# SCH_Genie-V1_2024-08-11.net
KiCad netlist of a schematic drawn in EasyEDA
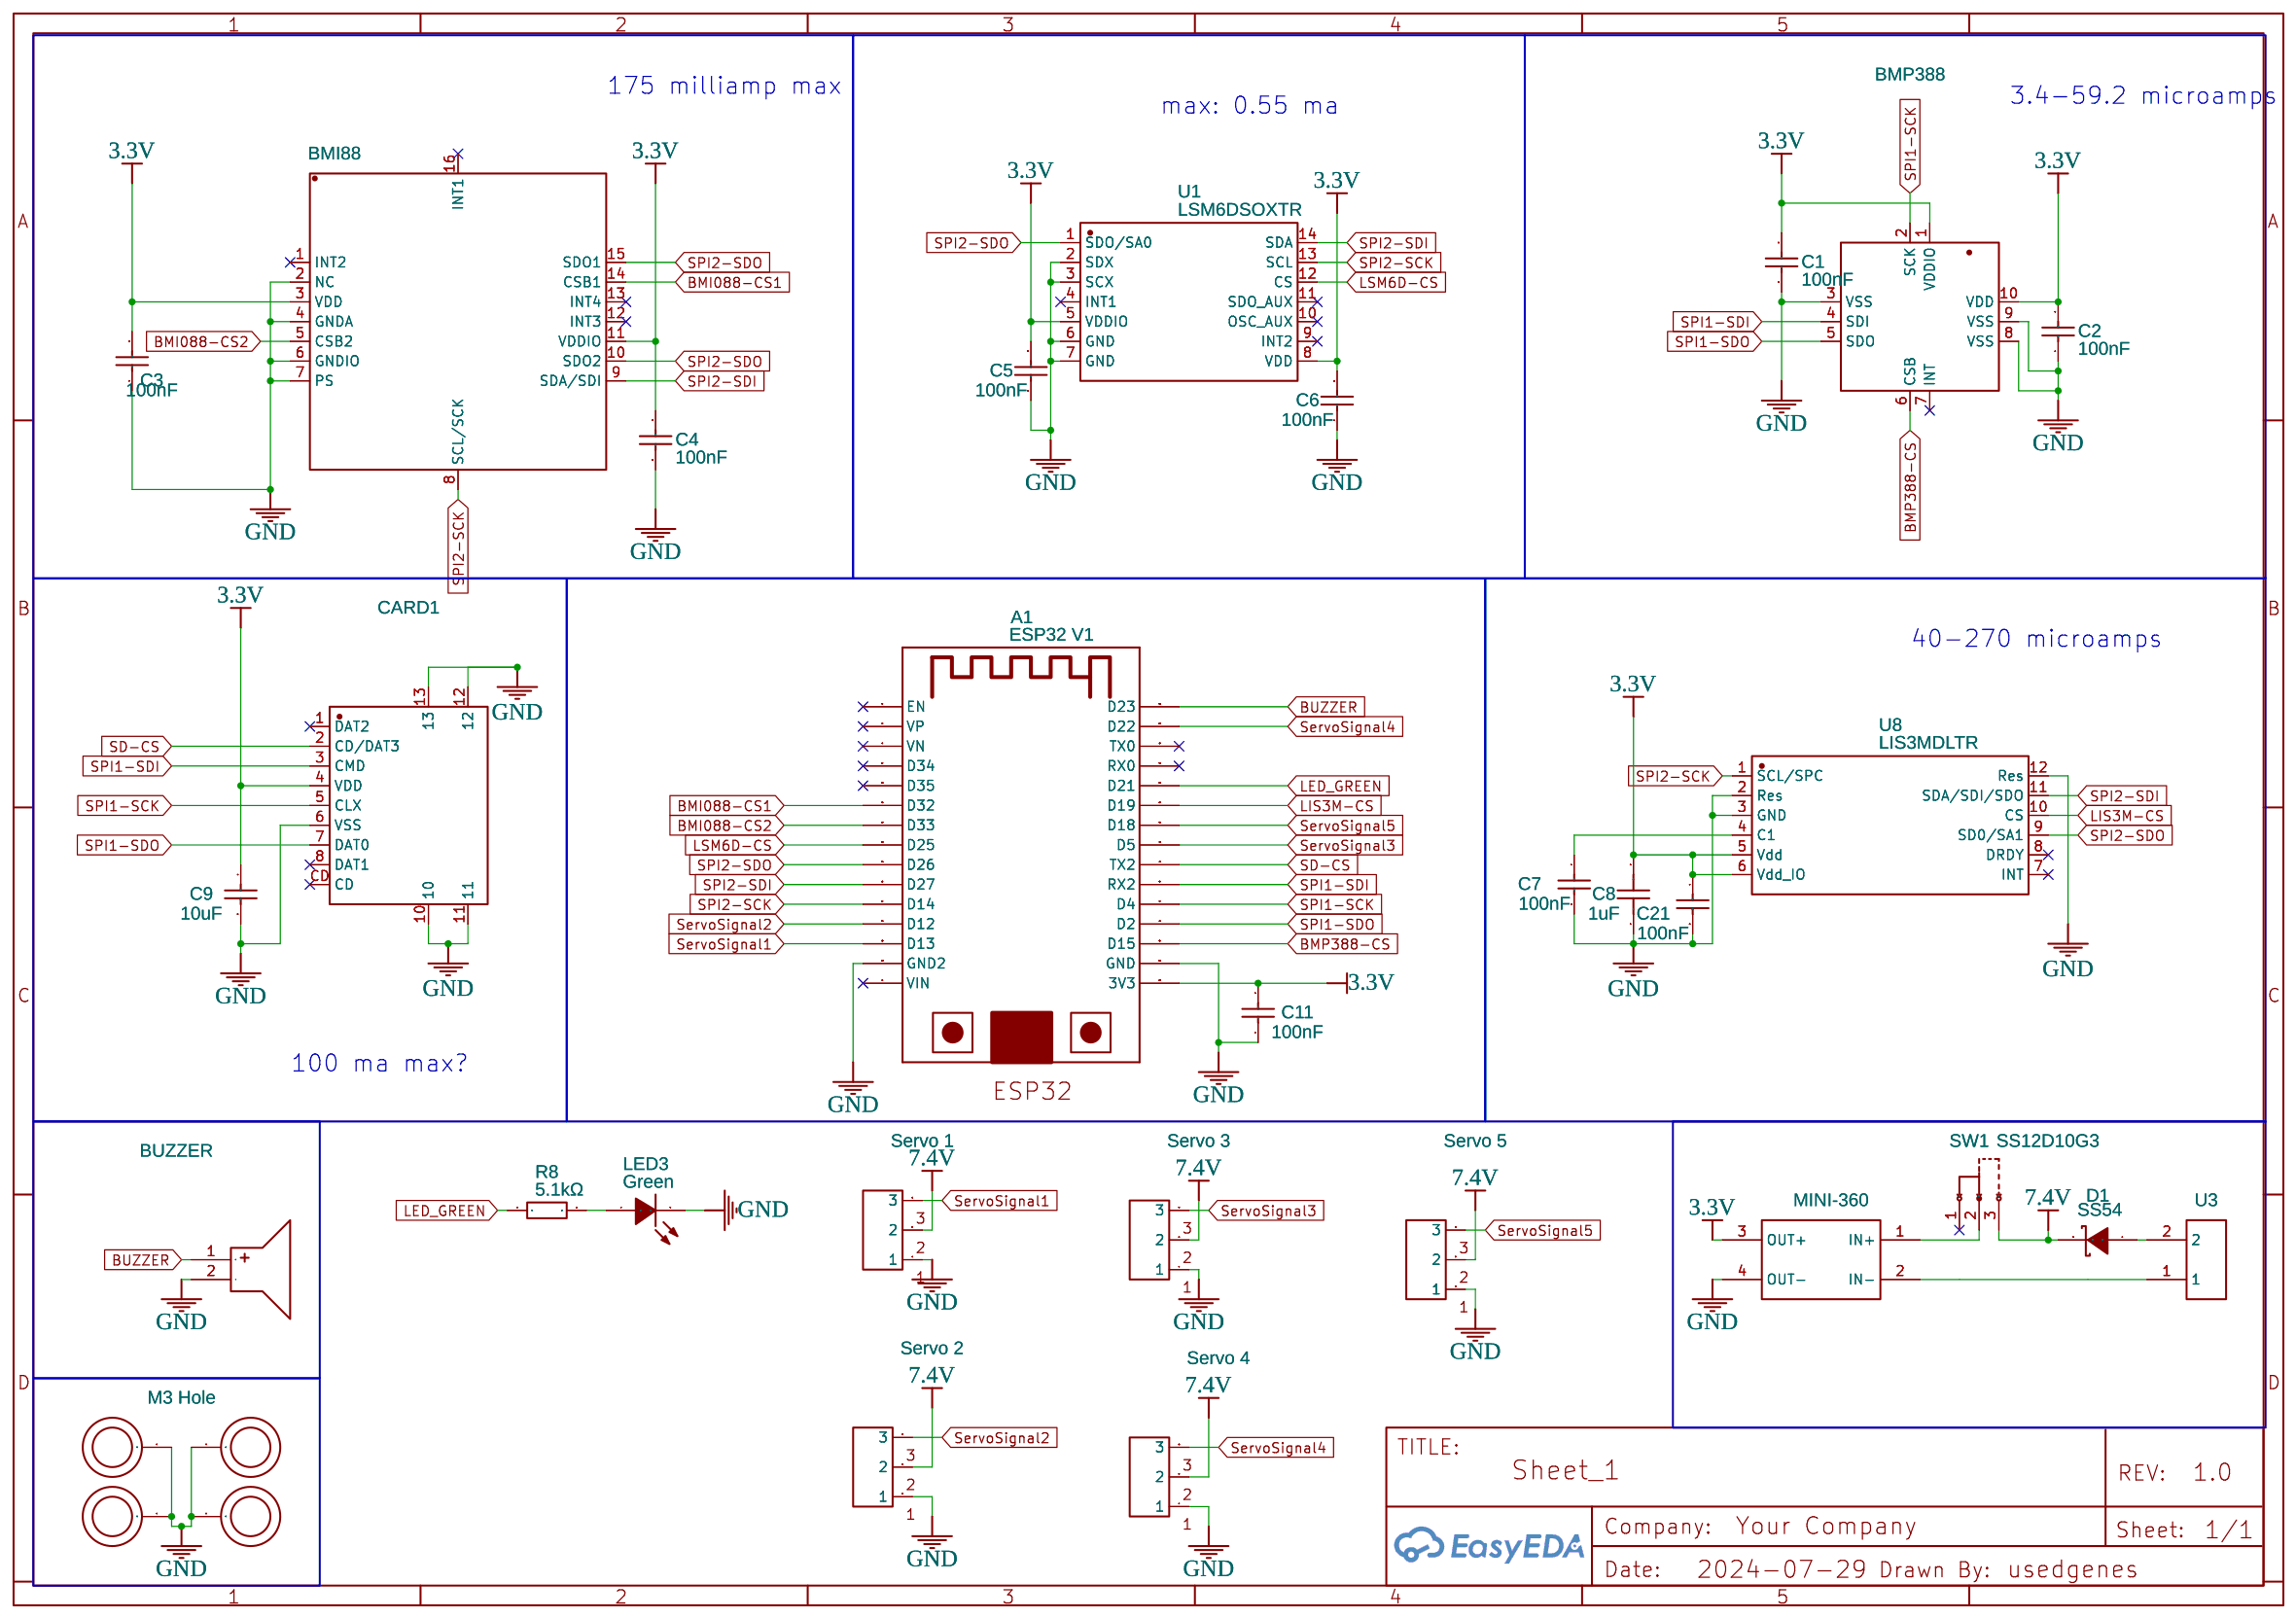
[diagram p0: schematic sheet]

(export (version "E")
  (design (tool "Eeschema 10.0.6"))
  (components
    (comp (ref "A1") (value "ESP32 V1") (libsource (lib "") (part "ESP32-DEVKIT-V1-30PIN")))
    (comp (ref "BMI88")
      (value "BMI088")
      (fields (field (name "Manufacturer") "Bosch(博世)"))
      (libsource (lib "") (part "BMI088"))
    )
    (comp (ref "BMP388")
      (value "BMP388")
      (fields (field (name "Manufacturer") "Bosch(博世)"))
      (libsource (lib "") (part "BMP388"))
    )
    (comp (ref "BUZZER")
      (value "4000Hz")
      (fields
        (field (name "Manufacturer Part") "SKY-1475-0540-45P7.6")
        (field (name "Manufacturer") "S&S(海旭)")
      )
      (libsource (lib "") (part "SKY-1475-0540-45P7.6"))
    )
    (comp (ref "C1")
      (value "100nF")
      (fields
        (field (name "Manufacturer Part") "CL05B104KO5NNNC")
        (field (name "Manufacturer") "SAMSUNG(三星)")
      )
      (libsource (lib "") (part "CL05B104KO5NNNC"))
    )
    (comp (ref "C2")
      (value "100nF")
      (fields
        (field (name "Manufacturer Part") "CL05B104KO5NNNC")
        (field (name "Manufacturer") "SAMSUNG(三星)")
      )
      (libsource (lib "") (part "CL05B104KO5NNNC"))
    )
    (comp (ref "C3")
      (value "100nF")
      (fields
        (field (name "Manufacturer Part") "CL05B104KO5NNNC")
        (field (name "Manufacturer") "SAMSUNG(三星)")
      )
      (libsource (lib "") (part "CL05B104KO5NNNC"))
    )
    (comp (ref "C4")
      (value "100nF")
      (fields
        (field (name "Manufacturer Part") "CL05B104KO5NNNC")
        (field (name "Manufacturer") "SAMSUNG(三星)")
      )
      (libsource (lib "") (part "CL05B104KO5NNNC"))
    )
    (comp (ref "C5")
      (value "100nF")
      (fields
        (field (name "Manufacturer Part") "CL05B104KO5NNNC")
        (field (name "Manufacturer") "SAMSUNG(三星)")
      )
      (libsource (lib "") (part "CL05B104KO5NNNC"))
    )
    (comp (ref "C6")
      (value "100nF")
      (fields
        (field (name "Manufacturer Part") "CL05B104KO5NNNC")
        (field (name "Manufacturer") "SAMSUNG(三星)")
      )
      (libsource (lib "") (part "CL05B104KO5NNNC"))
    )
    (comp (ref "C7")
      (value "100nF")
      (fields
        (field (name "Manufacturer Part") "CL05B104KO5NNNC")
        (field (name "Manufacturer") "SAMSUNG(三星)")
      )
      (libsource (lib "") (part "CL05B104KO5NNNC_1"))
    )
    (comp (ref "C8")
      (value "1uF")
      (fields
        (field (name "Manufacturer Part") "CL05A105KA5NQNC")
        (field (name "Manufacturer") "SAMSUNG(三星)")
      )
      (libsource (lib "") (part "CL05A105KA5NQNC"))
    )
    (comp (ref "C9")
      (value "10uF")
      (fields
        (field (name "Manufacturer Part") "CL05A106MQ5NUNC")
        (field (name "Manufacturer") "SAMSUNG(三星)")
      )
      (libsource (lib "") (part "CL05A106MQ5NUNC"))
    )
    (comp (ref "C11")
      (value "100nF")
      (fields
        (field (name "Manufacturer Part") "CL05B104KO5NNNC")
        (field (name "Manufacturer") "SAMSUNG(三星)")
      )
      (libsource (lib "") (part "CL05B104KO5NNNC"))
    )
    (comp (ref "C21")
      (value "100nF")
      (fields
        (field (name "Manufacturer Part") "CL05B104KO5NNNC")
        (field (name "Manufacturer") "SAMSUNG(三星)")
      )
      (libsource (lib "") (part "CL05B104KO5NNNC_1"))
    )
    (comp (ref "CARD1")
      (value "TF PUSH")
      (fields (field (name "Manufacturer") "SHOU HAN(首韩)"))
      (libsource (lib "") (part "TF PUSH"))
    )
    (comp (ref "D1")
      (value "SS54")
      (fields (field (name "Manufacturer") "MDD(辰达半导体)"))
      (libsource (lib "") (part "SS54_C22452"))
    )
    (comp (ref "H1") (value "M3 Hole") (libsource (lib "") (part "3MM_HOLE_1")))
    (comp (ref "H2") (value "3MM_HOLE") (libsource (lib "") (part "3MM_HOLE")))
    (comp (ref "H3") (value "3MM_HOLE") (libsource (lib "") (part "3MM_HOLE_1")))
    (comp (ref "H4") (value "3MM_HOLE") (libsource (lib "") (part "3MM_HOLE")))
    (comp (ref "LED3")
      (value "Green")
      (fields (field (name "Manufacturer Part") "KT-0805G") (field (name "Manufacturer") "KENTO"))
      (libsource (lib "") (part "0805G (Green)"))
    )
    (comp (ref "MINI-360") (value "MINI-360") (libsource (lib "") (part "MINI-360")))
    (comp (ref "P1")
      (value "Servo 2")
      (fields
        (field (name "Manufacturer Part") "Female headerHDR1X8-2.54")
        (field (name "Manufacturer") "BOOMELE")
      )
      (libsource (lib "") (part "HEADER PAD 3X RMM COPY"))
    )
    (comp (ref "P2")
      (value "Servo 1")
      (fields
        (field (name "Manufacturer Part") "Female headerHDR1X8-2.54")
        (field (name "Manufacturer") "BOOMELE")
      )
      (libsource (lib "") (part "HEADER PAD 3X RMM COPY"))
    )
    (comp (ref "P3")
      (value "Servo 3")
      (fields
        (field (name "Manufacturer Part") "Female headerHDR1X8-2.54")
        (field (name "Manufacturer") "BOOMELE")
      )
      (libsource (lib "") (part "HEADER PAD 3X RMM COPY"))
    )
    (comp (ref "P4")
      (value "Servo 5")
      (fields
        (field (name "Manufacturer Part") "Female headerHDR1X8-2.54")
        (field (name "Manufacturer") "BOOMELE")
      )
      (libsource (lib "") (part "HEADER PAD 3X RMM COPY"))
    )
    (comp (ref "P5")
      (value "Servo 4")
      (fields
        (field (name "Manufacturer Part") "Female headerHDR1X8-2.54")
        (field (name "Manufacturer") "BOOMELE")
      )
      (libsource (lib "") (part "HEADER PAD 3X RMM COPY"))
    )
    (comp (ref "R8")
      (value "5.1kΩ")
      (fields
        (field (name "Manufacturer Part") "0402WGF5101TCE")
        (field (name "Manufacturer") "UNI-ROYAL(厚声)")
      )
      (libsource (lib "") (part "0402WGF5101TCE"))
    )
    (comp (ref "SW1")
      (value "SS12D10G3")
      (fields (field (name "Manufacturer") "SHOU HAN(首韩)"))
      (libsource (lib "") (part "SS12D10G3"))
    )
    (comp (ref "U1")
      (value "LSM6DSOXTR")
      (fields (field (name "Manufacturer") "ST(意法半导体)"))
      (libsource (lib "") (part "LSM6DSOXTR"))
    )
    (comp (ref "U3") (value "Power Pins") (libsource (lib "") (part "1X2")))
    (comp (ref "U8")
      (value "LIS3MDLTR")
      (fields (field (name "Manufacturer") "ST(意法半导体)"))
      (libsource (lib "") (part "LIS3MDLTR"))
    )
  )
  (nets
    (net (code "1") (name "3.3V") (class "Default")
      (node (ref "A1") (pin "3V3") (pinfunction "3V3_3V3") (pintype "unspecified"))
      (node (ref "BMI88") (pin "11") (pinfunction "VDDIO_11") (pintype "unspecified"))
      (node (ref "BMI88") (pin "3") (pinfunction "VDD_3") (pintype "unspecified"))
      (node (ref "BMP388") (pin "1") (pinfunction "VDDIO_1") (pintype "unspecified"))
      (node (ref "BMP388") (pin "10") (pinfunction "VDD_10") (pintype "unspecified"))
      (node (ref "C1") (pin "2") (pinfunction "2_2") (pintype "input"))
      (node (ref "C11") (pin "2") (pinfunction "2_2") (pintype "input"))
      (node (ref "C2") (pin "2") (pinfunction "2_2") (pintype "input"))
      (node (ref "C21") (pin "1") (pinfunction "1_1") (pintype "input"))
      (node (ref "C3") (pin "2") (pinfunction "2_2") (pintype "input"))
      (node (ref "C4") (pin "2") (pinfunction "2_2") (pintype "input"))
      (node (ref "C5") (pin "2") (pinfunction "2_2") (pintype "input"))
      (node (ref "C6") (pin "2") (pinfunction "2_2") (pintype "input"))
      (node (ref "C8") (pin "2") (pinfunction "2_2") (pintype "unspecified"))
      (node (ref "C9") (pin "1") (pinfunction "1_1") (pintype "input"))
      (node (ref "CARD1") (pin "4") (pinfunction "VDD_4") (pintype "unspecified"))
      (node (ref "MINI-360") (pin "3") (pinfunction "OUT+_3") (pintype "unspecified"))
      (node (ref "U1") (pin "5") (pinfunction "VDDIO_5") (pintype "unspecified"))
      (node (ref "U1") (pin "8") (pinfunction "VDD_8") (pintype "unspecified"))
      (node (ref "U8") (pin "5") (pinfunction "Vdd_5") (pintype "unspecified"))
      (node (ref "U8") (pin "6") (pinfunction "Vdd_IO_6") (pintype "unspecified"))
    )
    (net (code "2") (name "7.4V") (class "Default")
      (node (ref "D1") (pin "2") (pinfunction "K_2") (pintype "unspecified"))
      (node (ref "P1") (pin "2") (pinfunction "2_2") (pintype "unspecified"))
      (node (ref "P2") (pin "2") (pinfunction "2_2") (pintype "unspecified"))
      (node (ref "P3") (pin "2") (pinfunction "2_2") (pintype "unspecified"))
      (node (ref "P4") (pin "2") (pinfunction "2_2") (pintype "unspecified"))
      (node (ref "P5") (pin "2") (pinfunction "2_2") (pintype "unspecified"))
      (node (ref "SW1") (pin "3") (pinfunction "3_3") (pintype "unspecified"))
    )
    (net (code "3") (name "BMI088-CS1") (class "Default")
      (node (ref "A1") (pin "D32") (pinfunction "D32_D32") (pintype "unspecified"))
      (node (ref "BMI88") (pin "14") (pinfunction "CSB1_14") (pintype "unspecified"))
    )
    (net (code "4") (name "BMI088-CS2") (class "Default")
      (node (ref "A1") (pin "D33") (pinfunction "D33_D33") (pintype "unspecified"))
      (node (ref "BMI88") (pin "5") (pinfunction "CSB2_5") (pintype "unspecified"))
    )
    (net (code "5") (name "BMP388-CS") (class "Default")
      (node (ref "A1") (pin "D15") (pinfunction "D15_D15") (pintype "unspecified"))
      (node (ref "BMP388") (pin "6") (pinfunction "CSB_6") (pintype "unspecified"))
    )
    (net (code "6") (name "BUZZER") (class "Default")
      (node (ref "A1") (pin "D23") (pinfunction "D23_D23") (pintype "unspecified"))
      (node (ref "BUZZER") (pin "1") (pinfunction "+_1") (pintype "unspecified"))
    )
    (net (code "7") (name "GND") (class "Default")
      (node (ref "A1") (pin "GND") (pinfunction "GND_GND") (pintype "unspecified"))
      (node (ref "A1") (pin "GND2") (pinfunction "GND2_GND2") (pintype "unspecified"))
      (node (ref "BMI88") (pin "2") (pinfunction "NC_2") (pintype "unspecified"))
      (node (ref "BMI88") (pin "4") (pinfunction "GNDA_4") (pintype "unspecified"))
      (node (ref "BMI88") (pin "6") (pinfunction "GNDIO_6") (pintype "unspecified"))
      (node (ref "BMI88") (pin "7") (pinfunction "PS_7") (pintype "unspecified"))
      (node (ref "BMP388") (pin "3") (pinfunction "VSS_3") (pintype "unspecified"))
      (node (ref "BMP388") (pin "8") (pinfunction "VSS_8") (pintype "unspecified"))
      (node (ref "BMP388") (pin "9") (pinfunction "VSS_9") (pintype "unspecified"))
      (node (ref "BUZZER") (pin "2") (pinfunction "-_2") (pintype "unspecified"))
      (node (ref "C1") (pin "1") (pinfunction "1_1") (pintype "input"))
      (node (ref "C11") (pin "1") (pinfunction "1_1") (pintype "input"))
      (node (ref "C2") (pin "1") (pinfunction "1_1") (pintype "input"))
      (node (ref "C21") (pin "2") (pinfunction "2_2") (pintype "input"))
      (node (ref "C3") (pin "1") (pinfunction "1_1") (pintype "input"))
      (node (ref "C4") (pin "1") (pinfunction "1_1") (pintype "input"))
      (node (ref "C5") (pin "1") (pinfunction "1_1") (pintype "input"))
      (node (ref "C6") (pin "1") (pinfunction "1_1") (pintype "input"))
      (node (ref "C7") (pin "2") (pinfunction "2_2") (pintype "input"))
      (node (ref "C8") (pin "1") (pinfunction "1_1") (pintype "unspecified"))
      (node (ref "C9") (pin "2") (pinfunction "2_2") (pintype "input"))
      (node (ref "CARD1") (pin "10") (pinfunction "10_10") (pintype "unspecified"))
      (node (ref "CARD1") (pin "11") (pinfunction "11_11") (pintype "unspecified"))
      (node (ref "CARD1") (pin "12") (pinfunction "12_12") (pintype "unspecified"))
      (node (ref "CARD1") (pin "13") (pinfunction "13_13") (pintype "unspecified"))
      (node (ref "CARD1") (pin "6") (pinfunction "VSS_6") (pintype "unspecified"))
      (node (ref "H1") (pin "1") (pinfunction "1_1") (pintype "bidirectional"))
      (node (ref "H2") (pin "1") (pinfunction "1_1") (pintype "bidirectional"))
      (node (ref "H3") (pin "1") (pinfunction "1_1") (pintype "bidirectional"))
      (node (ref "H4") (pin "1") (pinfunction "1_1") (pintype "bidirectional"))
      (node (ref "LED3") (pin "2") (pinfunction "K_2") (pintype "unspecified"))
      (node (ref "MINI-360") (pin "4") (pinfunction "OUT-_4") (pintype "unspecified"))
      (node (ref "P1") (pin "1") (pinfunction "1_1") (pintype "unspecified"))
      (node (ref "P2") (pin "1") (pinfunction "1_1") (pintype "unspecified"))
      (node (ref "P3") (pin "1") (pinfunction "1_1") (pintype "unspecified"))
      (node (ref "P4") (pin "1") (pinfunction "1_1") (pintype "unspecified"))
      (node (ref "P5") (pin "1") (pinfunction "1_1") (pintype "unspecified"))
      (node (ref "U1") (pin "2") (pinfunction "SDX_2") (pintype "unspecified"))
      (node (ref "U1") (pin "3") (pinfunction "SCX_3") (pintype "unspecified"))
      (node (ref "U1") (pin "6") (pinfunction "GND_6") (pintype "unspecified"))
      (node (ref "U1") (pin "7") (pinfunction "GND_7") (pintype "unspecified"))
      (node (ref "U8") (pin "12") (pinfunction "Res_12") (pintype "unspecified"))
      (node (ref "U8") (pin "2") (pinfunction "Res_2") (pintype "unspecified"))
      (node (ref "U8") (pin "3") (pinfunction "GND_3") (pintype "unspecified"))
    )
    (net (code "8") (name "LED_GREEN") (class "Default")
      (node (ref "A1") (pin "D21") (pinfunction "D21_D21") (pintype "unspecified"))
      (node (ref "R8") (pin "1") (pinfunction "1_1") (pintype "input"))
    )
    (net (code "9") (name "LIS3M-CS") (class "Default")
      (node (ref "A1") (pin "D19") (pinfunction "D19_D19") (pintype "unspecified"))
      (node (ref "U8") (pin "10") (pinfunction "CS_10") (pintype "unspecified"))
    )
    (net (code "10") (name "LSM6D-CS") (class "Default")
      (node (ref "A1") (pin "D25") (pinfunction "D25_D25") (pintype "unspecified"))
      (node (ref "U1") (pin "12") (pinfunction "CS_12") (pintype "unspecified"))
    )
    (net (code "11") (name "Net-(D1-A)") (class "Default")
      (node (ref "D1") (pin "1") (pinfunction "A_1") (pintype "unspecified"))
      (node (ref "U3") (pin "2") (pinfunction "2_2") (pintype "unspecified"))
    )
    (net (code "12") (name "Net-(LED3-A)") (class "Default")
      (node (ref "LED3") (pin "1") (pinfunction "A_1") (pintype "unspecified"))
      (node (ref "R8") (pin "2") (pinfunction "2_2") (pintype "input"))
    )
    (net (code "13") (name "Net-(MINI-360-IN+)") (class "Default")
      (node (ref "MINI-360") (pin "1") (pinfunction "IN+_1") (pintype "unspecified"))
      (node (ref "SW1") (pin "2") (pinfunction "2_2") (pintype "unspecified"))
    )
    (net (code "14") (name "Net-(MINI-360-IN-)") (class "Default")
      (node (ref "MINI-360") (pin "2") (pinfunction "IN-_2") (pintype "unspecified"))
      (node (ref "U3") (pin "1") (pinfunction "1_1") (pintype "unspecified"))
    )
    (net (code "15") (name "Net-(U8-C1)") (class "Default")
      (node (ref "C7") (pin "1") (pinfunction "1_1") (pintype "input"))
      (node (ref "U8") (pin "4") (pinfunction "C1_4") (pintype "unspecified"))
    )
    (net (code "16") (name "SD-CS") (class "Default")
      (node (ref "A1") (pin "TX2") (pinfunction "TX2_TX2") (pintype "unspecified"))
      (node (ref "CARD1") (pin "2") (pinfunction "CD/DAT3_2") (pintype "unspecified"))
    )
    (net (code "17") (name "SPI1-SCK") (class "Default")
      (node (ref "A1") (pin "D4") (pinfunction "D4_D4") (pintype "unspecified"))
      (node (ref "BMP388") (pin "2") (pinfunction "SCK_2") (pintype "unspecified"))
      (node (ref "CARD1") (pin "5") (pinfunction "CLX_5") (pintype "unspecified"))
    )
    (net (code "18") (name "SPI1-SDI") (class "Default")
      (node (ref "A1") (pin "RX2") (pinfunction "RX2_RX2") (pintype "unspecified"))
      (node (ref "BMP388") (pin "4") (pinfunction "SDI_4") (pintype "unspecified"))
      (node (ref "CARD1") (pin "3") (pinfunction "CMD_3") (pintype "unspecified"))
    )
    (net (code "19") (name "SPI1-SDO") (class "Default")
      (node (ref "A1") (pin "D2") (pinfunction "D2_D2") (pintype "unspecified"))
      (node (ref "BMP388") (pin "5") (pinfunction "SDO_5") (pintype "unspecified"))
      (node (ref "CARD1") (pin "7") (pinfunction "DAT0_7") (pintype "unspecified"))
    )
    (net (code "20") (name "SPI2-SCK") (class "Default")
      (node (ref "A1") (pin "D14") (pinfunction "D14_D14") (pintype "unspecified"))
      (node (ref "BMI88") (pin "8") (pinfunction "SCL/SCK_8") (pintype "unspecified"))
      (node (ref "U1") (pin "13") (pinfunction "SCL_13") (pintype "unspecified"))
      (node (ref "U8") (pin "1") (pinfunction "SCL/SPC_1") (pintype "unspecified"))
    )
    (net (code "21") (name "SPI2-SDI") (class "Default")
      (node (ref "A1") (pin "D27") (pinfunction "D27_D27") (pintype "unspecified"))
      (node (ref "BMI88") (pin "9") (pinfunction "SDA/SDI_9") (pintype "unspecified"))
      (node (ref "U1") (pin "14") (pinfunction "SDA_14") (pintype "unspecified"))
      (node (ref "U8") (pin "11") (pinfunction "SDA/SDI/SDO_11") (pintype "unspecified"))
    )
    (net (code "22") (name "SPI2-SDO") (class "Default")
      (node (ref "A1") (pin "D26") (pinfunction "D26_D26") (pintype "unspecified"))
      (node (ref "BMI88") (pin "10") (pinfunction "SDO2_10") (pintype "unspecified"))
      (node (ref "BMI88") (pin "15") (pinfunction "SDO1_15") (pintype "unspecified"))
      (node (ref "U1") (pin "1") (pinfunction "SDO/SA0_1") (pintype "unspecified"))
      (node (ref "U8") (pin "9") (pinfunction "SD0/SA1_9") (pintype "unspecified"))
    )
    (net (code "23") (name "ServoSignal1") (class "Default")
      (node (ref "A1") (pin "D13") (pinfunction "D13_D13") (pintype "unspecified"))
      (node (ref "P2") (pin "3") (pinfunction "3_3") (pintype "unspecified"))
    )
    (net (code "24") (name "ServoSignal2") (class "Default")
      (node (ref "A1") (pin "D12") (pinfunction "D12_D12") (pintype "unspecified"))
      (node (ref "P1") (pin "3") (pinfunction "3_3") (pintype "unspecified"))
    )
    (net (code "25") (name "ServoSignal3") (class "Default")
      (node (ref "A1") (pin "D5") (pinfunction "D5_D5") (pintype "unspecified"))
      (node (ref "P3") (pin "3") (pinfunction "3_3") (pintype "unspecified"))
    )
    (net (code "26") (name "ServoSignal4") (class "Default")
      (node (ref "A1") (pin "D22") (pinfunction "D22_D22") (pintype "unspecified"))
      (node (ref "P5") (pin "3") (pinfunction "3_3") (pintype "unspecified"))
    )
    (net (code "27") (name "ServoSignal5") (class "Default")
      (node (ref "A1") (pin "D18") (pinfunction "D18_D18") (pintype "unspecified"))
      (node (ref "P4") (pin "3") (pinfunction "3_3") (pintype "unspecified"))
    )
    (net (code "28") (name "unconnected-(A1-PadD34)") (class "Default")
      (node (ref "A1") (pin "D34") (pinfunction "D34_D34") (pintype "unspecified+no_connect"))
    )
    (net (code "29") (name "unconnected-(A1-PadD35)") (class "Default")
      (node (ref "A1") (pin "D35") (pinfunction "D35_D35") (pintype "unspecified+no_connect"))
    )
    (net (code "30") (name "unconnected-(A1-PadEN)") (class "Default")
      (node (ref "A1") (pin "EN") (pinfunction "EN_EN") (pintype "unspecified+no_connect"))
    )
    (net (code "31") (name "unconnected-(A1-PadRX0)") (class "Default")
      (node (ref "A1") (pin "RX0") (pinfunction "RX0_RX0") (pintype "unspecified+no_connect"))
    )
    (net (code "32") (name "unconnected-(A1-PadTX0)") (class "Default")
      (node (ref "A1") (pin "TX0") (pinfunction "TX0_TX0") (pintype "unspecified+no_connect"))
    )
    (net (code "33") (name "unconnected-(A1-PadVIN)") (class "Default")
      (node (ref "A1") (pin "VIN") (pinfunction "VIN_VIN") (pintype "unspecified+no_connect"))
    )
    (net (code "34") (name "unconnected-(A1-PadVN)") (class "Default")
      (node (ref "A1") (pin "VN") (pinfunction "VN_VN") (pintype "unspecified+no_connect"))
    )
    (net (code "35") (name "unconnected-(A1-PadVP)") (class "Default")
      (node (ref "A1") (pin "VP") (pinfunction "VP_VP") (pintype "unspecified+no_connect"))
    )
    (net (code "36") (name "unconnected-(BMI88-INT1-Pad16)") (class "Default")
      (node (ref "BMI88") (pin "16") (pinfunction "INT1_16") (pintype "unspecified+no_connect"))
    )
    (net (code "37") (name "unconnected-(BMI88-INT2-Pad1)") (class "Default")
      (node (ref "BMI88") (pin "1") (pinfunction "INT2_1") (pintype "unspecified+no_connect"))
    )
    (net (code "38") (name "unconnected-(BMI88-INT3-Pad12)") (class "Default")
      (node (ref "BMI88") (pin "12") (pinfunction "INT3_12") (pintype "unspecified+no_connect"))
    )
    (net (code "39") (name "unconnected-(BMI88-INT4-Pad13)") (class "Default")
      (node (ref "BMI88") (pin "13") (pinfunction "INT4_13") (pintype "unspecified+no_connect"))
    )
    (net (code "40") (name "unconnected-(BMP388-INT-Pad7)") (class "Default")
      (node (ref "BMP388") (pin "7") (pinfunction "INT_7") (pintype "unspecified+no_connect"))
    )
    (net (code "41") (name "unconnected-(CARD1-DAT1-Pad8)") (class "Default")
      (node (ref "CARD1") (pin "8") (pinfunction "DAT1_8") (pintype "unspecified+no_connect"))
    )
    (net (code "42") (name "unconnected-(CARD1-DAT2-Pad1)") (class "Default")
      (node (ref "CARD1") (pin "1") (pinfunction "DAT2_1") (pintype "unspecified+no_connect"))
    )
    (net (code "43") (name "unconnected-(CARD1-PadCD)") (class "Default")
      (node (ref "CARD1") (pin "CD") (pinfunction "CD_CD") (pintype "unspecified+no_connect"))
    )
    (net (code "44") (name "unconnected-(SW1-Pad1)") (class "Default")
      (node (ref "SW1") (pin "1") (pinfunction "1_1") (pintype "unspecified+no_connect"))
    )
    (net (code "45") (name "unconnected-(U1-INT1-Pad4)") (class "Default")
      (node (ref "U1") (pin "4") (pinfunction "INT1_4") (pintype "unspecified+no_connect"))
    )
    (net (code "46") (name "unconnected-(U1-INT2-Pad9)") (class "Default")
      (node (ref "U1") (pin "9") (pinfunction "INT2_9") (pintype "unspecified+no_connect"))
    )
    (net (code "47") (name "unconnected-(U1-OSC_AUX-Pad10)") (class "Default")
      (node (ref "U1") (pin "10") (pinfunction "OSC_AUX_10") (pintype "unspecified+no_connect"))
    )
    (net (code "48") (name "unconnected-(U1-SDO_AUX-Pad11)") (class "Default")
      (node (ref "U1") (pin "11") (pinfunction "SDO_AUX_11") (pintype "unspecified+no_connect"))
    )
    (net (code "49") (name "unconnected-(U8-DRDY-Pad8)") (class "Default")
      (node (ref "U8") (pin "8") (pinfunction "DRDY_8") (pintype "unspecified+no_connect"))
    )
    (net (code "50") (name "unconnected-(U8-INT-Pad7)") (class "Default")
      (node (ref "U8") (pin "7") (pinfunction "INT_7") (pintype "unspecified+no_connect"))
    )
  )
)
